# Alimentacion.net
KiCad netlist of a schematic drawn in Altium Designer
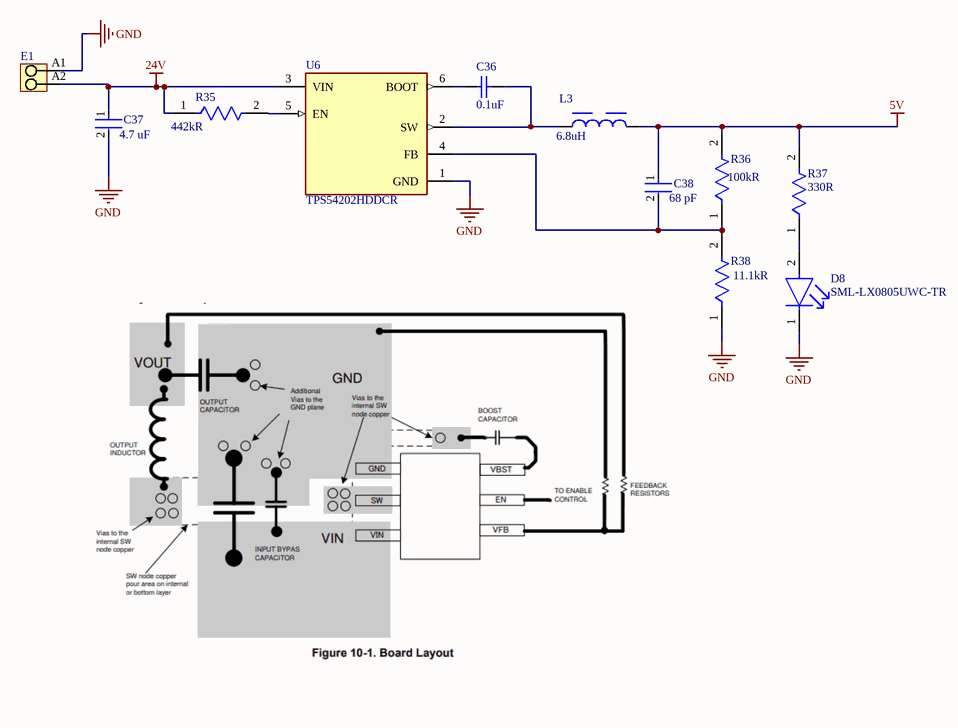
[diagram p0: Alimentacion.SchDoc]

(export (version "E")
  (design (tool "Eeschema 10.0.6"))
  (components
    (comp (ref "C36")
      (value "0.1uF")
      (footprint "CAPC1005X60X30ML05T10")
      (fields (field (name "PART NUMBER") "C0402C104M9RACTU") (field (name "MANUFACTURER") "Kemet"))
      (libsource (lib "Altium Content Vault") (part "CAP"))
    )
    (comp (ref "C37")
      (value "4.7 uF")
      (footprint "FP-CC0805-0_85-MFG")
      (description "CAP CER 4.7UF 50V X5R 0805")
      (fields (field (name "TOLERANCE") "0.1") (field (name "MANUFACTURER") "Yageo"))
      (libsource (lib "Altium Content Vault") (part "11868f565c42a9108669ba33697ecf6"))
    )
    (comp (ref "C38")
      (value "68 pF")
      (footprint "FP-C0402-BB-MFG")
      (description "C0402 68 pF X8R 5.00% 50 V")
      (fields
        (field (name "TOLERANCE") "0.05")
        (field (name "OCTOPART") "https://octopart.com/c0402c680j5hactu-kemet-88724668")
      )
      (libsource (lib "Altium Content Vault") (part "b4654b650e69147ec39a6b967a45e02"))
    )
    (comp (ref "D8")
      (value "SML-LX0805UWC-TR")
      (footprint "FP-SML-LX0805UWC-TR-MFG")
      (description "SML-LX0805UWC-TR White LED, 0805 Diffused, Rectangle Lens SMD package")
      (libsource (lib "Altium Content Vault") (part "8706943c75ba83719d021d2fdc84c58"))
    )
    (comp (ref "E1")
      (value "1330710000")
      (footprint "LMF_5_08_90_02")
      (description "OMNIMATE Signal - series LMF")
      (fields (field (name "MANUFACTURER") "Weidmueller"))
      (libsource (lib "Altium Content Vault") (part "Terminal_02_1x02"))
    )
    (comp (ref "L3")
      (value "6.8uH")
      (footprint "WE-MAPI_3020")
      (description "Power Inductor, 6.8UH, Shielded, 2A Rohs Compliant: Yes")
      (fields (field (name "Comment") "74438336068HT"))
      (libsource (lib "Altium Content Vault") (part "Inductor - 3"))
    )
    (comp (ref "R35")
      (value "CRCW0603442KFKEC")
      (footprint "FP-CRCW0603-e3-IPC_C")
      (description "RES Thick Film, 442kΩ, 1%, 0.1W, 100ppm/°C, 0603")
      (fields (field (name "RESISTANCE") "442kR") (field (name "TOLERANCE") "1%"))
      (libsource (lib "Altium Content Vault") (part "1029c3af85768c4190bb7ad29bc67b5"))
    )
    (comp (ref "R36")
      (value "CRGP0603F100K")
      (footprint "FP-CRGP0603-IPC_C")
      (description "CRGP 0603 100K 1%")
      (fields
        (field (name "MANUFACTURER") "TE")
        (field (name "OCTOPART") "https://octopart.com/crgp0603f100k-te+connectivity-91018719")
        (field (name "RESISTANCE") "100kR")
      )
      (libsource (lib "Altium Content Vault") (part "1029c3af85768c4190bb7ad29bc67b5"))
    )
    (comp (ref "R37")
      (value "AC0603JR-07330RL")
      (footprint "FP-AC0603-IPC_C")
      (description "RES 330Ω 5.00% 0.1W 0603")
      (fields (field (name "TOLERANCE") "5%") (field (name "RESISTANCE") "330R"))
      (libsource (lib "Altium Content Vault") (part "1029c3af85768c4190bb7ad29bc67b5"))
    )
    (comp (ref "R38")
      (value "11.1kR")
      (footprint "FP-RN73R1E-IPC_A")
      (description "11.1kΩ ±0.1% 0.063W, 1/16W Chip Resistor 0402 (1005 Metric) Moisture Resistant Thin Film")
      (fields (field (name "Comment") "RN73R1ETTP1112B25"))
      (libsource (lib "Altium Content Vault") (part "1029c3af85768c4190bb7ad29bc67b5"))
    )
    (comp (ref "U6")
      (value "TPS54202HDDCR")
      (footprint "FP-DDC0006A-IPC_B")
      (description "IC REG BUCK ADJ 2A TSOT23-6")
      (libsource (lib "Altium Content Vault") (part "25a96549b0aea5692a3f4b7350c7a76"))
    )
  )
  (nets
    (net (code "1") (name "5V") (class "Default")
      (node (ref "C38") (pin "1") (pinfunction "1_1") (pintype "passive"))
      (node (ref "L3") (pin "2") (pinfunction "2_2") (pintype "passive"))
      (node (ref "R36") (pin "2") (pinfunction "2_2") (pintype "passive"))
      (node (ref "R37") (pin "2") (pinfunction "2_2") (pintype "passive"))
    )
    (net (code "2") (name "24V") (class "Default")
      (node (ref "C37") (pin "1") (pinfunction "1_1") (pintype "passive"))
      (node (ref "E1") (pin "A2") (pinfunction "A2_A2") (pintype "passive"))
      (node (ref "R35") (pin "1") (pinfunction "1_1") (pintype "passive"))
      (node (ref "U6") (pin "3") (pinfunction "VIN_3") (pintype "power_in"))
    )
    (net (code "3") (name "GND") (class "Default")
      (node (ref "C37") (pin "2") (pinfunction "2_2") (pintype "passive"))
      (node (ref "D8") (pin "1") (pinfunction "C_1") (pintype "passive"))
      (node (ref "E1") (pin "A1") (pinfunction "A1_A1") (pintype "passive"))
      (node (ref "R38") (pin "1") (pinfunction "1_1") (pintype "passive"))
      (node (ref "U6") (pin "1") (pinfunction "GND_1") (pintype "power_in"))
    )
    (net (code "4") (name "Net-(D8-A)") (class "Default")
      (node (ref "D8") (pin "2") (pinfunction "A_2") (pintype "passive"))
      (node (ref "R37") (pin "1") (pinfunction "1_1") (pintype "passive"))
    )
    (net (code "5") (name "Net-(U6-BOOT)") (class "Default")
      (node (ref "C36") (pin "2") (pinfunction "2_2") (pintype "passive"))
      (node (ref "U6") (pin "6") (pinfunction "BOOT_6") (pintype "output"))
    )
    (net (code "6") (name "Net-(U6-EN)") (class "Default")
      (node (ref "R35") (pin "2") (pinfunction "2_2") (pintype "passive"))
      (node (ref "U6") (pin "5") (pinfunction "EN_5") (pintype "input"))
    )
    (net (code "7") (name "Net-(U6-FB)") (class "Default")
      (node (ref "C38") (pin "2") (pinfunction "2_2") (pintype "passive"))
      (node (ref "R36") (pin "1") (pinfunction "1_1") (pintype "passive"))
      (node (ref "R38") (pin "2") (pinfunction "2_2") (pintype "passive"))
      (node (ref "U6") (pin "4") (pinfunction "FB_4") (pintype "passive"))
    )
    (net (code "8") (name "Net-(U6-SW)") (class "Default")
      (node (ref "C36") (pin "1") (pinfunction "1_1") (pintype "passive"))
      (node (ref "L3") (pin "1") (pinfunction "1_1") (pintype "passive"))
      (node (ref "U6") (pin "2") (pinfunction "SW_2") (pintype "output"))
    )
  )
)
